# Plantemoji.net
KiCad netlist of a schematic drawn in EAGLE
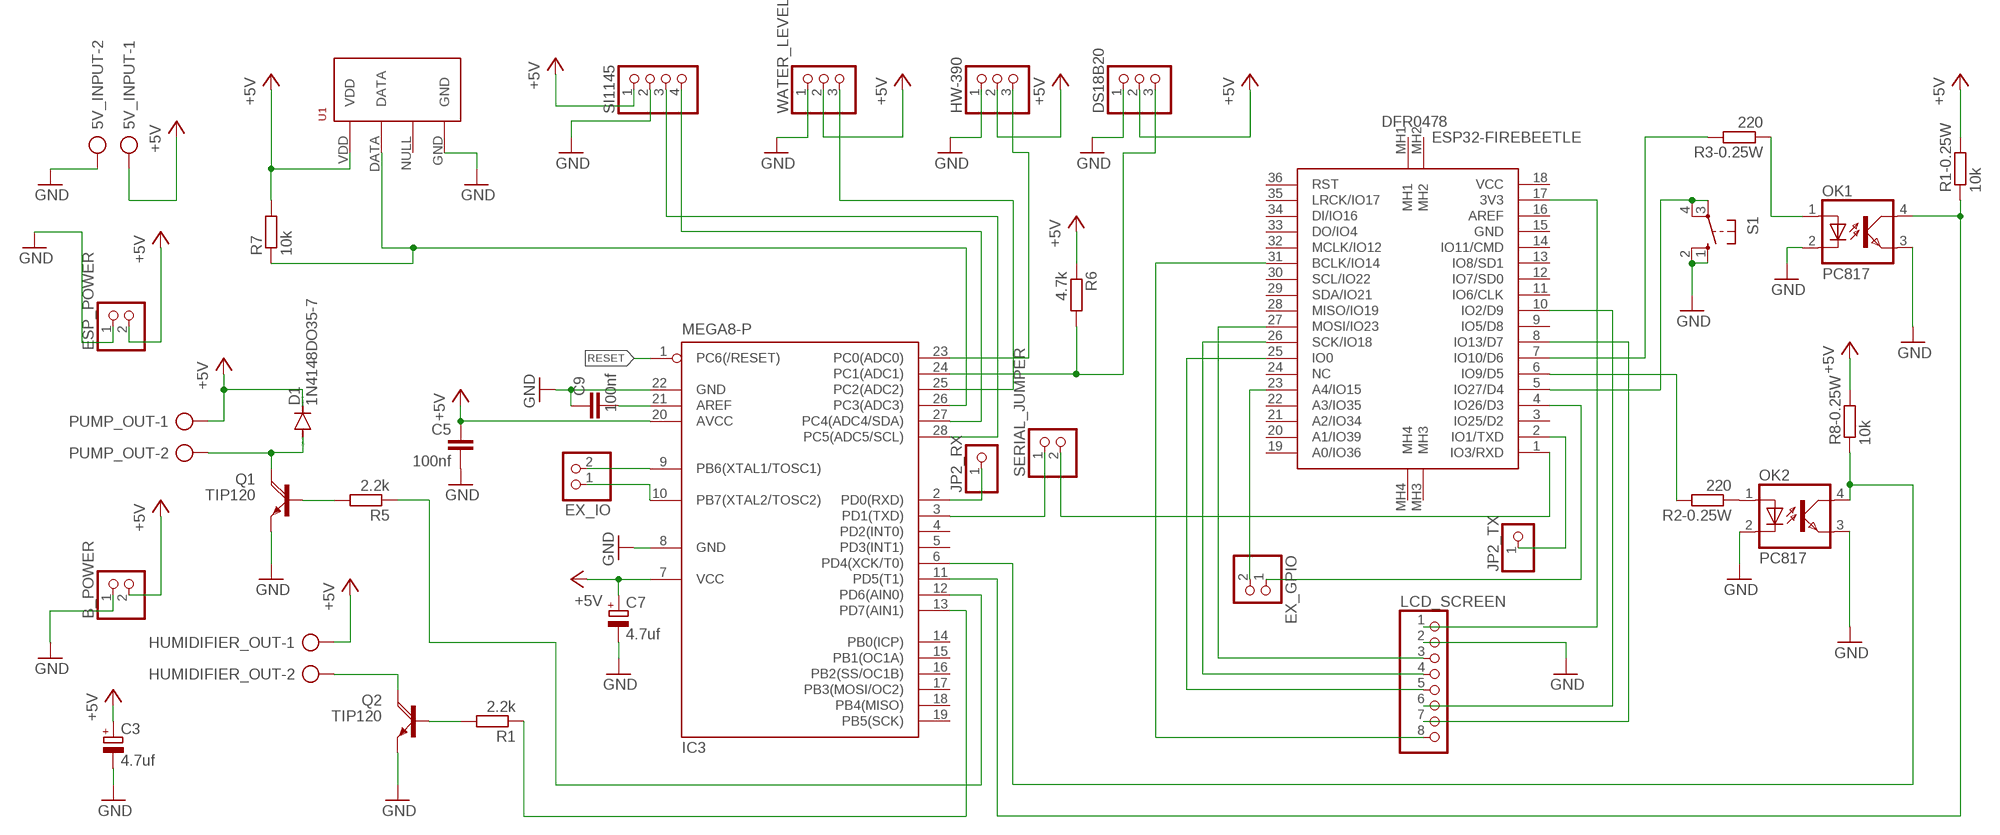
[diagram p0: schematic, sheet 1]

(export (version "E")
  (design (tool "Eeschema 10.0.6"))
  (components
    (comp (ref "5V_INPUT")
      (value "AK500/2")
      (footprint "eagle-import:AK500_2")
      (libsource (lib "eagle-import") (part "AK500/2"))
    )
    (comp (ref "B_POWER")
      (value "PINHD-1X2")
      (footprint "eagle-import:1X02")
      (libsource (lib "eagle-import") (part "PINHD-1X2"))
    )
    (comp (ref "C3")
      (value "4.7uf")
      (footprint "eagle-import:E2,5-5")
      (libsource (lib "eagle-import") (part "CPOL-EUE2.5-5"))
    )
    (comp (ref "C5")
      (value "100nf")
      (footprint "eagle-import:C025-025X050")
      (libsource (lib "eagle-import") (part "C-EU025-025X050"))
    )
    (comp (ref "C7")
      (value "4.7uf")
      (footprint "eagle-import:E2,5-5")
      (libsource (lib "eagle-import") (part "CPOL-EUE2.5-5"))
    )
    (comp (ref "C9")
      (value "100nf")
      (footprint "eagle-import:C025-025X050")
      (libsource (lib "eagle-import") (part "C-EU025-025X050"))
    )
    (comp (ref "D1")
      (value "1N4148DO35-7")
      (footprint "eagle-import:DO35-7")
      (libsource (lib "eagle-import") (part "1N4148DO35-7"))
    )
    (comp (ref "DS18B20")
      (value "PINHD-1X3")
      (footprint "eagle-import:1X03")
      (libsource (lib "eagle-import") (part "PINHD-1X3"))
    )
    (comp (ref "ESP32-FIREBEETLE")
      (value "DFR0478")
      (footprint "eagle-import:FIREBEETLE_ESP32")
      (fields (field (name "MOUSER_PART_NUMBER") "426-DFR0478"))
      (libsource (lib "eagle-import") (part "DFR0478"))
    )
    (comp (ref "ESP_POWER")
      (value "PINHD-1X2")
      (footprint "eagle-import:1X02")
      (libsource (lib "eagle-import") (part "PINHD-1X2"))
    )
    (comp (ref "EX_GPIO")
      (value "PINHD-1X2")
      (footprint "eagle-import:1X02")
      (libsource (lib "eagle-import") (part "PINHD-1X2"))
    )
    (comp (ref "EX_IO")
      (value "PINHD-1X2")
      (footprint "eagle-import:1X02")
      (libsource (lib "eagle-import") (part "PINHD-1X2"))
    )
    (comp (ref "HUMIDIFIER_OUT")
      (value "AK500/2")
      (footprint "eagle-import:AK500_2")
      (libsource (lib "eagle-import") (part "AK500/2"))
    )
    (comp (ref "HW-390")
      (value "PINHD-1X3")
      (footprint "eagle-import:1X03")
      (libsource (lib "eagle-import") (part "PINHD-1X3"))
    )
    (comp (ref "IC3")
      (value "MEGA8-P")
      (footprint "eagle-import:DIL28-3")
      (libsource (lib "eagle-import") (part "MEGA8-P"))
    )
    (comp (ref "JP2_RX")
      (value "PINHD-1X1")
      (footprint "eagle-import:1X01")
      (libsource (lib "eagle-import") (part "PINHD-1X1"))
    )
    (comp (ref "JP2_TX")
      (value "PINHD-1X1")
      (footprint "eagle-import:1X01")
      (libsource (lib "eagle-import") (part "PINHD-1X1"))
    )
    (comp (ref "LCD_SCREEN")
      (value "PINHD-1X8")
      (footprint "eagle-import:1X08")
      (libsource (lib "eagle-import") (part "PINHD-1X8"))
    )
    (comp (ref "OK1")
      (value "PC817")
      (footprint "eagle-import:DIL04")
      (fields (field (name "MPN") "PC817X4J000F"))
      (libsource (lib "eagle-import") (part "PC817"))
    )
    (comp (ref "OK2")
      (value "PC817")
      (footprint "eagle-import:DIL04")
      (fields (field (name "MPN") "PC817X4J000F"))
      (libsource (lib "eagle-import") (part "PC817"))
    )
    (comp (ref "PUMP_OUT")
      (value "AK500/2")
      (footprint "eagle-import:AK500_2")
      (libsource (lib "eagle-import") (part "AK500/2"))
    )
    (comp (ref "Q1")
      (value "TIP120")
      (footprint "eagle-import:TO220AH")
      (libsource (lib "eagle-import") (part "TIP120"))
    )
    (comp (ref "Q2")
      (value "TIP120")
      (footprint "eagle-import:TO220AH")
      (libsource (lib "eagle-import") (part "TIP120"))
    )
    (comp (ref "R1")
      (value "2.2k")
      (footprint "eagle-import:0207_10")
      (libsource (lib "eagle-import") (part "R-EU_0207/10"))
    )
    (comp (ref "R1-0.25W")
      (value "10k")
      (footprint "eagle-import:0207_10")
      (libsource (lib "eagle-import") (part "R-EU_0207/10"))
    )
    (comp (ref "R2-0.25W")
      (value "220")
      (footprint "eagle-import:0207_10")
      (libsource (lib "eagle-import") (part "R-EU_0207/10"))
    )
    (comp (ref "R3-0.25W")
      (value "220")
      (footprint "eagle-import:0207_10")
      (libsource (lib "eagle-import") (part "R-EU_0207/10"))
    )
    (comp (ref "R5")
      (value "2.2k")
      (footprint "eagle-import:0207_10")
      (libsource (lib "eagle-import") (part "R-EU_0207/10"))
    )
    (comp (ref "R6")
      (value "4.7k")
      (footprint "eagle-import:0207_10")
      (libsource (lib "eagle-import") (part "R-EU_0207/10"))
    )
    (comp (ref "R7")
      (value "10k")
      (footprint "eagle-import:0207_10")
      (libsource (lib "eagle-import") (part "R-EU_0207/10"))
    )
    (comp (ref "R8-0.25W")
      (value "10k")
      (footprint "eagle-import:0207_10")
      (libsource (lib "eagle-import") (part "R-EU_0207/10"))
    )
    (comp (ref "S1")
      (value "10-XX")
      (footprint "eagle-import:B3F-10XX")
      (fields (field (name "MPN") "B3F-1000"))
      (libsource (lib "eagle-import") (part "10-XX"))
    )
    (comp (ref "SERIAL_JUMPER")
      (value "PINHD-1X2")
      (footprint "eagle-import:1X02")
      (libsource (lib "eagle-import") (part "PINHD-1X2"))
    )
    (comp (ref "SI1145")
      (value "PINHD-1X4")
      (footprint "eagle-import:1X04")
      (libsource (lib "eagle-import") (part "PINHD-1X4"))
    )
    (comp (ref "U1")
      (value "RHT03_DHT-22_AM2302")
      (footprint "eagle-import:RHT03_DHT-22")
      (libsource (lib "eagle-import") (part "RHT03_DHT-22_AM2302"))
    )
    (comp (ref "WATER_LEVEL")
      (value "PINHD-1X3")
      (footprint "eagle-import:1X03")
      (libsource (lib "eagle-import") (part "PINHD-1X3"))
    )
  )
  (nets
    (net (code "1") (name "+5V") (class "Default")
      (node (ref "5V_INPUT") (pin "1") (pinfunction "KL_1") (pintype "passive"))
      (node (ref "B_POWER") (pin "2") (pinfunction "2_2") (pintype "passive"))
      (node (ref "C3") (pin "+") (pinfunction "+_+") (pintype "passive"))
      (node (ref "C5") (pin "1") (pinfunction "1_1") (pintype "passive"))
      (node (ref "C7") (pin "+") (pinfunction "+_+") (pintype "passive"))
      (node (ref "D1") (pin "C") (pinfunction "C_C") (pintype "passive"))
      (node (ref "DS18B20") (pin "2") (pinfunction "2_2") (pintype "passive"))
      (node (ref "ESP_POWER") (pin "2") (pinfunction "2_2") (pintype "passive"))
      (node (ref "HUMIDIFIER_OUT") (pin "1") (pinfunction "KL_1") (pintype "passive"))
      (node (ref "HW-390") (pin "2") (pinfunction "2_2") (pintype "passive"))
      (node (ref "IC3") (pin "20") (pinfunction "AVCC_20") (pintype "power_in"))
      (node (ref "IC3") (pin "7") (pinfunction "VCC_7") (pintype "power_in"))
      (node (ref "PUMP_OUT") (pin "1") (pinfunction "KL_1") (pintype "passive"))
      (node (ref "R1-0.25W") (pin "2") (pinfunction "2_2") (pintype "passive"))
      (node (ref "R6") (pin "1") (pinfunction "1_1") (pintype "passive"))
      (node (ref "R7") (pin "2") (pinfunction "2_2") (pintype "passive"))
      (node (ref "R8-0.25W") (pin "2") (pinfunction "2_2") (pintype "passive"))
      (node (ref "SI1145") (pin "1") (pinfunction "1_1") (pintype "passive"))
      (node (ref "U1") (pin "VDD") (pinfunction "VDD_VDD") (pintype "power_in"))
      (node (ref "WATER_LEVEL") (pin "2") (pinfunction "2_2") (pintype "passive"))
    )
    (net (code "2") (name "GND") (class "Default")
      (node (ref "5V_INPUT") (pin "2") (pinfunction "KL_2") (pintype "passive"))
      (node (ref "B_POWER") (pin "1") (pinfunction "1_1") (pintype "passive"))
      (node (ref "C3") (pin "-") (pinfunction "-_-") (pintype "passive"))
      (node (ref "C5") (pin "2") (pinfunction "2_2") (pintype "passive"))
      (node (ref "C7") (pin "-") (pinfunction "-_-") (pintype "passive"))
      (node (ref "C9") (pin "2") (pinfunction "2_2") (pintype "passive"))
      (node (ref "DS18B20") (pin "1") (pinfunction "1_1") (pintype "passive"))
      (node (ref "ESP_POWER") (pin "1") (pinfunction "1_1") (pintype "passive"))
      (node (ref "HW-390") (pin "1") (pinfunction "1_1") (pintype "passive"))
      (node (ref "IC3") (pin "22") (pinfunction "GND_22") (pintype "power_in"))
      (node (ref "IC3") (pin "8") (pinfunction "GND_8") (pintype "power_in"))
      (node (ref "LCD_SCREEN") (pin "2") (pinfunction "2_2") (pintype "passive"))
      (node (ref "OK1") (pin "2") (pinfunction "C_2") (pintype "passive"))
      (node (ref "OK1") (pin "3") (pinfunction "EMIT_3") (pintype "passive"))
      (node (ref "OK2") (pin "2") (pinfunction "C_2") (pintype "passive"))
      (node (ref "OK2") (pin "3") (pinfunction "EMIT_3") (pintype "passive"))
      (node (ref "Q1") (pin "E") (pinfunction "E_E") (pintype "passive"))
      (node (ref "Q2") (pin "E") (pinfunction "E_E") (pintype "passive"))
      (node (ref "S1") (pin "1") (pinfunction "S_1") (pintype "passive"))
      (node (ref "S1") (pin "2") (pinfunction "S1_2") (pintype "passive"))
      (node (ref "SI1145") (pin "2") (pinfunction "2_2") (pintype "passive"))
      (node (ref "U1") (pin "GND") (pinfunction "GND_GND") (pintype "power_in"))
      (node (ref "WATER_LEVEL") (pin "1") (pinfunction "1_1") (pintype "passive"))
    )
    (net (code "3") (name "Net-(ESP32-FIREBEETLE-3V3)") (class "Default")
      (node (ref "ESP32-FIREBEETLE") (pin "17") (pinfunction "3V3_17") (pintype "bidirectional"))
      (node (ref "LCD_SCREEN") (pin "1") (pinfunction "1_1") (pintype "passive"))
    )
    (net (code "4") (name "Net-(ESP32-FIREBEETLE-A4{slash}IO15)") (class "Default")
      (node (ref "ESP32-FIREBEETLE") (pin "23") (pinfunction "A4/IO15_23") (pintype "bidirectional"))
      (node (ref "EX_GPIO") (pin "2") (pinfunction "2_2") (pintype "passive"))
    )
    (net (code "5") (name "Net-(ESP32-FIREBEETLE-BCLK{slash}IO14)") (class "Default")
      (node (ref "ESP32-FIREBEETLE") (pin "31") (pinfunction "BCLK/IO14_31") (pintype "bidirectional"))
      (node (ref "LCD_SCREEN") (pin "8") (pinfunction "8_8") (pintype "passive"))
    )
    (net (code "6") (name "Net-(ESP32-FIREBEETLE-IO0)") (class "Default")
      (node (ref "ESP32-FIREBEETLE") (pin "25") (pinfunction "IO0_25") (pintype "bidirectional"))
      (node (ref "LCD_SCREEN") (pin "5") (pinfunction "5_5") (pintype "passive"))
    )
    (net (code "7") (name "Net-(ESP32-FIREBEETLE-IO1{slash}TXD)") (class "Default")
      (node (ref "ESP32-FIREBEETLE") (pin "2") (pinfunction "IO1/TXD_2") (pintype "bidirectional"))
      (node (ref "JP2_TX") (pin "1") (pinfunction "1_1") (pintype "passive"))
    )
    (net (code "8") (name "Net-(ESP32-FIREBEETLE-IO2{slash}D9)") (class "Default")
      (node (ref "ESP32-FIREBEETLE") (pin "10") (pinfunction "IO2/D9_10") (pintype "bidirectional"))
      (node (ref "LCD_SCREEN") (pin "6") (pinfunction "6_6") (pintype "passive"))
    )
    (net (code "9") (name "Net-(ESP32-FIREBEETLE-IO3{slash}RXD)") (class "Default")
      (node (ref "ESP32-FIREBEETLE") (pin "1") (pinfunction "IO3/RXD_1") (pintype "bidirectional"))
      (node (ref "SERIAL_JUMPER") (pin "2") (pinfunction "2_2") (pintype "passive"))
    )
    (net (code "10") (name "Net-(ESP32-FIREBEETLE-IO9{slash}D5)") (class "Default")
      (node (ref "ESP32-FIREBEETLE") (pin "6") (pinfunction "IO9/D5_6") (pintype "bidirectional"))
      (node (ref "R2-0.25W") (pin "2") (pinfunction "2_2") (pintype "passive"))
    )
    (net (code "11") (name "Net-(ESP32-FIREBEETLE-IO10{slash}D6)") (class "Default")
      (node (ref "ESP32-FIREBEETLE") (pin "7") (pinfunction "IO10/D6_7") (pintype "bidirectional"))
      (node (ref "R3-0.25W") (pin "2") (pinfunction "2_2") (pintype "passive"))
    )
    (net (code "12") (name "Net-(ESP32-FIREBEETLE-IO13{slash}D7)") (class "Default")
      (node (ref "ESP32-FIREBEETLE") (pin "8") (pinfunction "IO13/D7_8") (pintype "bidirectional"))
      (node (ref "LCD_SCREEN") (pin "7") (pinfunction "7_7") (pintype "passive"))
    )
    (net (code "13") (name "Net-(ESP32-FIREBEETLE-IO26{slash}D3)") (class "Default")
      (node (ref "ESP32-FIREBEETLE") (pin "4") (pinfunction "IO26/D3_4") (pintype "bidirectional"))
      (node (ref "EX_GPIO") (pin "1") (pinfunction "1_1") (pintype "passive"))
    )
    (net (code "14") (name "Net-(ESP32-FIREBEETLE-IO27{slash}D4)") (class "Default")
      (node (ref "ESP32-FIREBEETLE") (pin "5") (pinfunction "IO27/D4_5") (pintype "bidirectional"))
      (node (ref "S1") (pin "3") (pinfunction "P_3") (pintype "passive"))
      (node (ref "S1") (pin "4") (pinfunction "P1_4") (pintype "passive"))
    )
    (net (code "15") (name "Net-(ESP32-FIREBEETLE-MOSI{slash}IO23)") (class "Default")
      (node (ref "ESP32-FIREBEETLE") (pin "27") (pinfunction "MOSI/IO23_27") (pintype "bidirectional"))
      (node (ref "LCD_SCREEN") (pin "3") (pinfunction "3_3") (pintype "passive"))
    )
    (net (code "16") (name "Net-(ESP32-FIREBEETLE-SCK{slash}IO18)") (class "Default")
      (node (ref "ESP32-FIREBEETLE") (pin "26") (pinfunction "SCK/IO18_26") (pintype "bidirectional"))
      (node (ref "LCD_SCREEN") (pin "4") (pinfunction "4_4") (pintype "passive"))
    )
    (net (code "17") (name "Net-(HUMIDIFIER_OUTB-KL)") (class "Default")
      (node (ref "HUMIDIFIER_OUT") (pin "2") (pinfunction "KL_2") (pintype "passive"))
      (node (ref "Q2") (pin "C") (pinfunction "C_C") (pintype "passive"))
    )
    (net (code "18") (name "Net-(IC3-AREF)") (class "Default")
      (node (ref "C9") (pin "1") (pinfunction "1_1") (pintype "passive"))
      (node (ref "IC3") (pin "21") (pinfunction "AREF_21") (pintype "passive"))
    )
    (net (code "19") (name "Net-(IC3-PB6(XTAL1{slash}TOSC1))") (class "Default")
      (node (ref "EX_IO") (pin "2") (pinfunction "2_2") (pintype "passive"))
      (node (ref "IC3") (pin "9") (pinfunction "PB6(XTAL1/TOSC1)_9") (pintype "bidirectional"))
    )
    (net (code "20") (name "Net-(IC3-PB7(XTAL2{slash}TOSC2))") (class "Default")
      (node (ref "EX_IO") (pin "1") (pinfunction "1_1") (pintype "passive"))
      (node (ref "IC3") (pin "10") (pinfunction "PB7(XTAL2/TOSC2)_10") (pintype "bidirectional"))
    )
    (net (code "21") (name "Net-(IC3-PC0(ADC0))") (class "Default")
      (node (ref "HW-390") (pin "3") (pinfunction "3_3") (pintype "passive"))
      (node (ref "IC3") (pin "23") (pinfunction "PC0(ADC0)_23") (pintype "bidirectional"))
    )
    (net (code "22") (name "Net-(IC3-PC1(ADC1))") (class "Default")
      (node (ref "DS18B20") (pin "3") (pinfunction "3_3") (pintype "passive"))
      (node (ref "IC3") (pin "24") (pinfunction "PC1(ADC1)_24") (pintype "bidirectional"))
      (node (ref "R6") (pin "2") (pinfunction "2_2") (pintype "passive"))
    )
    (net (code "23") (name "Net-(IC3-PC2(ADC2))") (class "Default")
      (node (ref "IC3") (pin "25") (pinfunction "PC2(ADC2)_25") (pintype "bidirectional"))
      (node (ref "WATER_LEVEL") (pin "3") (pinfunction "3_3") (pintype "passive"))
    )
    (net (code "24") (name "Net-(IC3-PC3(ADC3))") (class "Default")
      (node (ref "IC3") (pin "26") (pinfunction "PC3(ADC3)_26") (pintype "bidirectional"))
      (node (ref "R7") (pin "1") (pinfunction "1_1") (pintype "passive"))
      (node (ref "U1") (pin "DATA") (pinfunction "DATA_DATA") (pintype "bidirectional"))
    )
    (net (code "25") (name "Net-(IC3-PC4(ADC4{slash}SDA))") (class "Default")
      (node (ref "IC3") (pin "27") (pinfunction "PC4(ADC4/SDA)_27") (pintype "bidirectional"))
      (node (ref "SI1145") (pin "4") (pinfunction "4_4") (pintype "passive"))
    )
    (net (code "26") (name "Net-(IC3-PC5(ADC5{slash}SCL))") (class "Default")
      (node (ref "IC3") (pin "28") (pinfunction "PC5(ADC5/SCL)_28") (pintype "bidirectional"))
      (node (ref "SI1145") (pin "3") (pinfunction "3_3") (pintype "passive"))
    )
    (net (code "27") (name "Net-(IC3-PD0(RXD))") (class "Default")
      (node (ref "IC3") (pin "2") (pinfunction "PD0(RXD)_2") (pintype "bidirectional"))
      (node (ref "JP2_RX") (pin "1") (pinfunction "1_1") (pintype "passive"))
    )
    (net (code "28") (name "Net-(IC3-PD1(TXD))") (class "Default")
      (node (ref "IC3") (pin "3") (pinfunction "PD1(TXD)_3") (pintype "bidirectional"))
      (node (ref "SERIAL_JUMPER") (pin "1") (pinfunction "1_1") (pintype "passive"))
    )
    (net (code "29") (name "Net-(IC3-PD4(XCK{slash}T0))") (class "Default")
      (node (ref "IC3") (pin "6") (pinfunction "PD4(XCK/T0)_6") (pintype "bidirectional"))
      (node (ref "OK2") (pin "4") (pinfunction "COL_4") (pintype "passive"))
      (node (ref "R8-0.25W") (pin "1") (pinfunction "1_1") (pintype "passive"))
    )
    (net (code "30") (name "Net-(IC3-PD5(T1))") (class "Default")
      (node (ref "IC3") (pin "11") (pinfunction "PD5(T1)_11") (pintype "bidirectional"))
      (node (ref "OK1") (pin "4") (pinfunction "COL_4") (pintype "passive"))
      (node (ref "R1-0.25W") (pin "1") (pinfunction "1_1") (pintype "passive"))
    )
    (net (code "31") (name "Net-(IC3-PD6(AIN0))") (class "Default")
      (node (ref "IC3") (pin "12") (pinfunction "PD6(AIN0)_12") (pintype "bidirectional"))
      (node (ref "R5") (pin "1") (pinfunction "1_1") (pintype "passive"))
    )
    (net (code "32") (name "Net-(IC3-PD7(AIN1))") (class "Default")
      (node (ref "IC3") (pin "13") (pinfunction "PD7(AIN1)_13") (pintype "bidirectional"))
      (node (ref "R1") (pin "1") (pinfunction "1_1") (pintype "passive"))
    )
    (net (code "33") (name "Net-(OK1-A)") (class "Default")
      (node (ref "OK1") (pin "1") (pinfunction "A_1") (pintype "passive"))
      (node (ref "R3-0.25W") (pin "1") (pinfunction "1_1") (pintype "passive"))
    )
    (net (code "34") (name "Net-(OK2-A)") (class "Default")
      (node (ref "OK2") (pin "1") (pinfunction "A_1") (pintype "passive"))
      (node (ref "R2-0.25W") (pin "1") (pinfunction "1_1") (pintype "passive"))
    )
    (net (code "35") (name "Net-(PUMP_OUTB-KL)") (class "Default")
      (node (ref "D1") (pin "A") (pinfunction "A_A") (pintype "passive"))
      (node (ref "PUMP_OUT") (pin "2") (pinfunction "KL_2") (pintype "passive"))
      (node (ref "Q1") (pin "C") (pinfunction "C_C") (pintype "passive"))
    )
    (net (code "36") (name "Net-(Q1-PadB)") (class "Default")
      (node (ref "Q1") (pin "B") (pinfunction "B_B") (pintype "passive"))
      (node (ref "R5") (pin "2") (pinfunction "2_2") (pintype "passive"))
    )
    (net (code "37") (name "Net-(Q2-PadB)") (class "Default")
      (node (ref "Q2") (pin "B") (pinfunction "B_B") (pintype "passive"))
      (node (ref "R1") (pin "2") (pinfunction "2_2") (pintype "passive"))
    )
    (net (code "38") (name "RESET") (class "Default")
      (node (ref "IC3") (pin "1") (pinfunction "PC6(/RESET)_1") (pintype "bidirectional"))
    )
    (net (code "39") (name "unconnected-(ESP32-FIREBEETLE-A0{slash}IO36-Pad19)") (class "Default")
      (node (ref "ESP32-FIREBEETLE") (pin "19") (pinfunction "A0/IO36_19") (pintype "bidirectional"))
    )
    (net (code "40") (name "unconnected-(ESP32-FIREBEETLE-A1{slash}IO39-Pad20)") (class "Default")
      (node (ref "ESP32-FIREBEETLE") (pin "20") (pinfunction "A1/IO39_20") (pintype "bidirectional"))
    )
    (net (code "41") (name "unconnected-(ESP32-FIREBEETLE-A2{slash}IO34-Pad21)") (class "Default")
      (node (ref "ESP32-FIREBEETLE") (pin "21") (pinfunction "A2/IO34_21") (pintype "bidirectional"))
    )
    (net (code "42") (name "unconnected-(ESP32-FIREBEETLE-A3{slash}IO35-Pad22)") (class "Default")
      (node (ref "ESP32-FIREBEETLE") (pin "22") (pinfunction "A3/IO35_22") (pintype "bidirectional"))
    )
    (net (code "43") (name "unconnected-(ESP32-FIREBEETLE-AREF-Pad16)") (class "Default")
      (node (ref "ESP32-FIREBEETLE") (pin "16") (pinfunction "AREF_16") (pintype "bidirectional"))
    )
    (net (code "44") (name "unconnected-(ESP32-FIREBEETLE-DI{slash}IO16-Pad34)") (class "Default")
      (node (ref "ESP32-FIREBEETLE") (pin "34") (pinfunction "DI/IO16_34") (pintype "bidirectional"))
    )
    (net (code "45") (name "unconnected-(ESP32-FIREBEETLE-DO{slash}IO4-Pad33)") (class "Default")
      (node (ref "ESP32-FIREBEETLE") (pin "33") (pinfunction "DO/IO4_33") (pintype "bidirectional"))
    )
    (net (code "46") (name "unconnected-(ESP32-FIREBEETLE-GND-Pad15)") (class "Default")
      (node (ref "ESP32-FIREBEETLE") (pin "15") (pinfunction "GND_15") (pintype "bidirectional"))
    )
    (net (code "47") (name "unconnected-(ESP32-FIREBEETLE-IO5{slash}D8-Pad9)") (class "Default")
      (node (ref "ESP32-FIREBEETLE") (pin "9") (pinfunction "IO5/D8_9") (pintype "bidirectional"))
    )
    (net (code "48") (name "unconnected-(ESP32-FIREBEETLE-IO6{slash}CLK-Pad11)") (class "Default")
      (node (ref "ESP32-FIREBEETLE") (pin "11") (pinfunction "IO6/CLK_11") (pintype "bidirectional"))
    )
    (net (code "49") (name "unconnected-(ESP32-FIREBEETLE-IO7{slash}SD0-Pad12)") (class "Default")
      (node (ref "ESP32-FIREBEETLE") (pin "12") (pinfunction "IO7/SD0_12") (pintype "bidirectional"))
    )
    (net (code "50") (name "unconnected-(ESP32-FIREBEETLE-IO8{slash}SD1-Pad13)") (class "Default")
      (node (ref "ESP32-FIREBEETLE") (pin "13") (pinfunction "IO8/SD1_13") (pintype "bidirectional"))
    )
    (net (code "51") (name "unconnected-(ESP32-FIREBEETLE-IO11{slash}CMD-Pad14)") (class "Default")
      (node (ref "ESP32-FIREBEETLE") (pin "14") (pinfunction "IO11/CMD_14") (pintype "bidirectional"))
    )
    (net (code "52") (name "unconnected-(ESP32-FIREBEETLE-IO25{slash}D2-Pad3)") (class "Default")
      (node (ref "ESP32-FIREBEETLE") (pin "3") (pinfunction "IO25/D2_3") (pintype "bidirectional"))
    )
    (net (code "53") (name "unconnected-(ESP32-FIREBEETLE-LRCK{slash}IO17-Pad35)") (class "Default")
      (node (ref "ESP32-FIREBEETLE") (pin "35") (pinfunction "LRCK/IO17_35") (pintype "bidirectional"))
    )
    (net (code "54") (name "unconnected-(ESP32-FIREBEETLE-MCLK{slash}IO12-Pad32)") (class "Default")
      (node (ref "ESP32-FIREBEETLE") (pin "32") (pinfunction "MCLK/IO12_32") (pintype "bidirectional"))
    )
    (net (code "55") (name "unconnected-(ESP32-FIREBEETLE-MISO{slash}IO19-Pad28)") (class "Default")
      (node (ref "ESP32-FIREBEETLE") (pin "28") (pinfunction "MISO/IO19_28") (pintype "bidirectional"))
    )
    (net (code "56") (name "unconnected-(ESP32-FIREBEETLE-NC-Pad24)") (class "Default")
      (node (ref "ESP32-FIREBEETLE") (pin "24") (pinfunction "NC_24") (pintype "no_connect"))
    )
    (net (code "57") (name "unconnected-(ESP32-FIREBEETLE-PadMH1)") (class "Default")
      (node (ref "ESP32-FIREBEETLE") (pin "MH1") (pinfunction "MH1_MH1") (pintype "bidirectional"))
    )
    (net (code "58") (name "unconnected-(ESP32-FIREBEETLE-PadMH2)") (class "Default")
      (node (ref "ESP32-FIREBEETLE") (pin "MH2") (pinfunction "MH2_MH2") (pintype "bidirectional"))
    )
    (net (code "59") (name "unconnected-(ESP32-FIREBEETLE-PadMH3)") (class "Default")
      (node (ref "ESP32-FIREBEETLE") (pin "MH3") (pinfunction "MH3_MH3") (pintype "bidirectional"))
    )
    (net (code "60") (name "unconnected-(ESP32-FIREBEETLE-PadMH4)") (class "Default")
      (node (ref "ESP32-FIREBEETLE") (pin "MH4") (pinfunction "MH4_MH4") (pintype "bidirectional"))
    )
    (net (code "61") (name "unconnected-(ESP32-FIREBEETLE-RST-Pad36)") (class "Default")
      (node (ref "ESP32-FIREBEETLE") (pin "36") (pinfunction "RST_36") (pintype "bidirectional"))
    )
    (net (code "62") (name "unconnected-(ESP32-FIREBEETLE-SCL{slash}IO22-Pad30)") (class "Default")
      (node (ref "ESP32-FIREBEETLE") (pin "30") (pinfunction "SCL/IO22_30") (pintype "bidirectional"))
    )
    (net (code "63") (name "unconnected-(ESP32-FIREBEETLE-SDA{slash}IO21-Pad29)") (class "Default")
      (node (ref "ESP32-FIREBEETLE") (pin "29") (pinfunction "SDA/IO21_29") (pintype "bidirectional"))
    )
    (net (code "64") (name "unconnected-(ESP32-FIREBEETLE-VCC-Pad18)") (class "Default")
      (node (ref "ESP32-FIREBEETLE") (pin "18") (pinfunction "VCC_18") (pintype "bidirectional"))
    )
    (net (code "65") (name "unconnected-(IC3-PB0(ICP)-Pad14)") (class "Default")
      (node (ref "IC3") (pin "14") (pinfunction "PB0(ICP)_14") (pintype "bidirectional"))
    )
    (net (code "66") (name "unconnected-(IC3-PB1(OC1A)-Pad15)") (class "Default")
      (node (ref "IC3") (pin "15") (pinfunction "PB1(OC1A)_15") (pintype "bidirectional"))
    )
    (net (code "67") (name "unconnected-(IC3-PB2(SS{slash}OC1B)-Pad16)") (class "Default")
      (node (ref "IC3") (pin "16") (pinfunction "PB2(SS/OC1B)_16") (pintype "bidirectional"))
    )
    (net (code "68") (name "unconnected-(IC3-PB3(MOSI{slash}OC2)-Pad17)") (class "Default")
      (node (ref "IC3") (pin "17") (pinfunction "PB3(MOSI/OC2)_17") (pintype "bidirectional"))
    )
    (net (code "69") (name "unconnected-(IC3-PB4(MISO)-Pad18)") (class "Default")
      (node (ref "IC3") (pin "18") (pinfunction "PB4(MISO)_18") (pintype "bidirectional"))
    )
    (net (code "70") (name "unconnected-(IC3-PB5(SCK)-Pad19)") (class "Default")
      (node (ref "IC3") (pin "19") (pinfunction "PB5(SCK)_19") (pintype "bidirectional"))
    )
    (net (code "71") (name "unconnected-(IC3-PD2(INT0)-Pad4)") (class "Default")
      (node (ref "IC3") (pin "4") (pinfunction "PD2(INT0)_4") (pintype "bidirectional"))
    )
    (net (code "72") (name "unconnected-(IC3-PD3(INT1)-Pad5)") (class "Default")
      (node (ref "IC3") (pin "5") (pinfunction "PD3(INT1)_5") (pintype "bidirectional"))
    )
    (net (code "73") (name "unconnected-(U1-PadNULL)") (class "Default")
      (node (ref "U1") (pin "NULL") (pinfunction "NULL_NULL") (pintype "no_connect"))
    )
  )
)
